# P04_USB_hub.net
KiCad netlist of a schematic drawn in Altium Designer
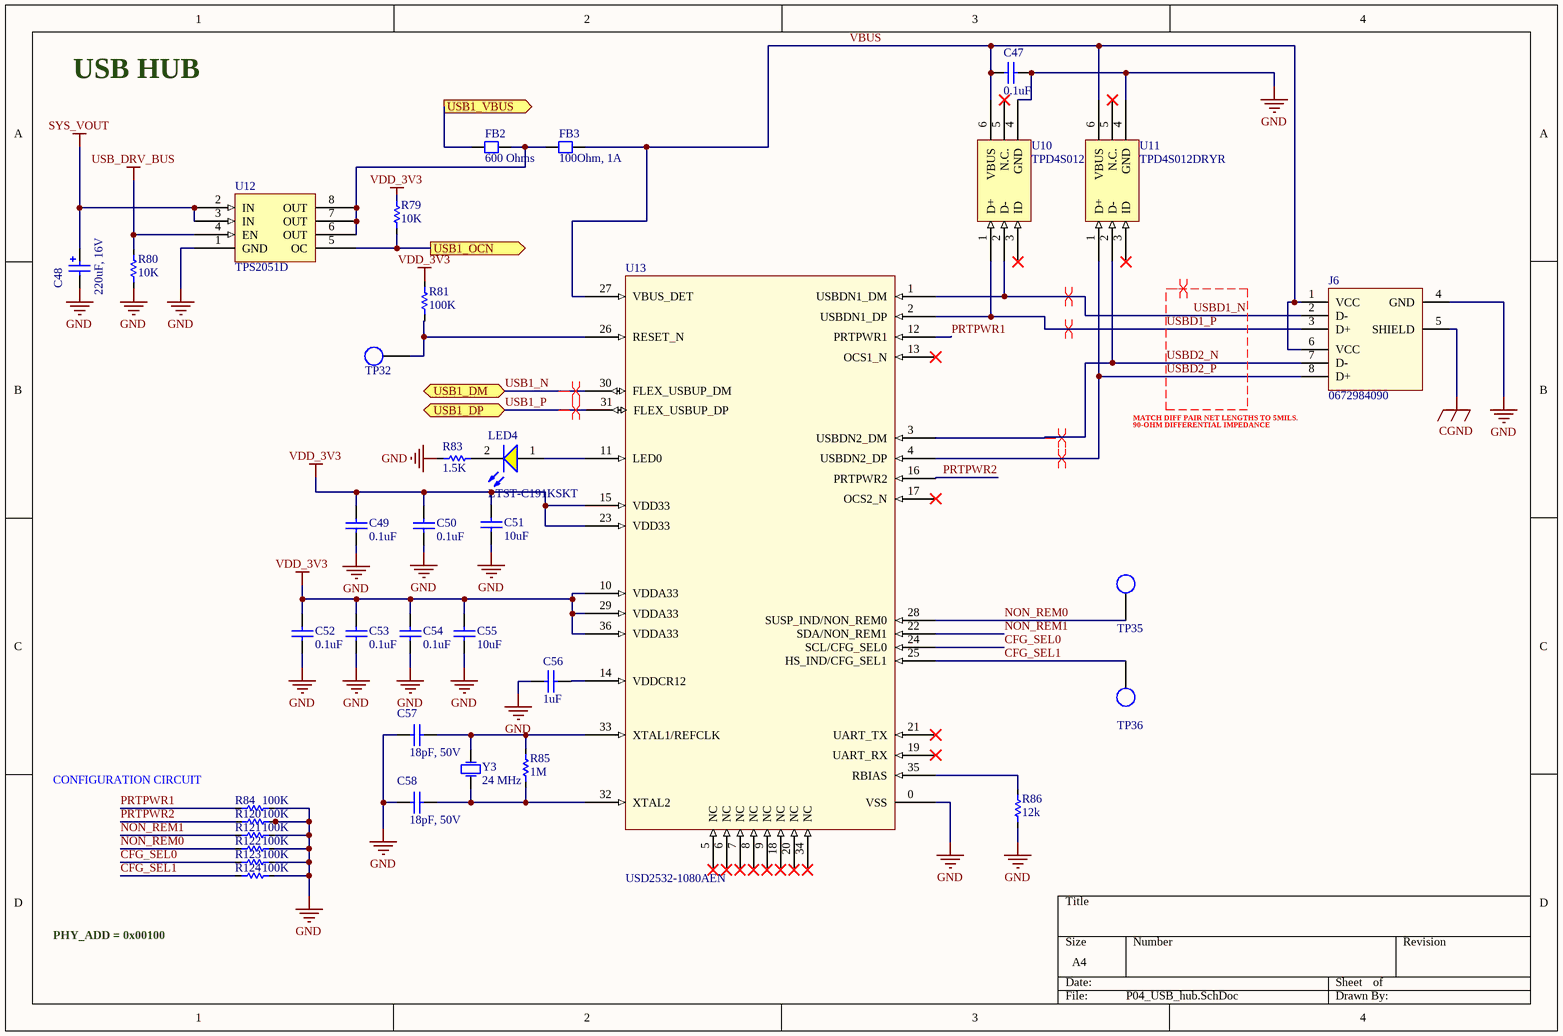
[diagram p0: P04_USB_hub.SchDoc]

(export (version "E")
  (design (tool "Eeschema 10.0.6"))
  (components
    (comp (ref "C47")
      (value "0.1uF")
      (footprint "CAP_0603")
      (description "CAP CER 0.1UF 16V X7R 0603")
      (fields (field (name "MANUFACTURER") "KEMET") (field (name "MANUFACTURER PART NO.") "C0603C104M4RACTU"))
      (libsource (lib "OSD335-X_Devboard") (part "C0603C104M4RACTU"))
    )
    (comp (ref "C48")
      (value "220uF, 16V")
      (footprint "CAP_SMD_6.3x7.7")
      (description "CAP 220 UF 20% 16 V")
      (fields
        (field (name "MANUFACTURER PART NO.") "865080345012")
        (field (name "MANUFACTURER") "Wurth Elektronik")
      )
      (libsource (lib "OSD335-X_Devboard") (part "865080345012"))
    )
    (comp (ref "C49")
      (value "0.1uF")
      (footprint "CAP_0603")
      (description "CAP CER 0.1UF 16V X7R 0603")
      (fields (field (name "MANUFACTURER") "KEMET") (field (name "MANUFACTURER PART NO.") "C0603C104M4RACTU"))
      (libsource (lib "OSD335-X_Devboard") (part "C0603C104M4RACTU"))
    )
    (comp (ref "C50")
      (value "0.1uF")
      (footprint "CAP_0603")
      (description "CAP CER 0.1UF 16V X7R 0603")
      (fields (field (name "MANUFACTURER") "KEMET") (field (name "MANUFACTURER PART NO.") "C0603C104M4RACTU"))
      (libsource (lib "OSD335-X_Devboard") (part "C0603C104M4RACTU"))
    )
    (comp (ref "C51")
      (value "10uF")
      (footprint "CAP_0603")
      (description "CAP CER 10UF 10V X5R 0603")
      (fields
        (field (name "MANUFACTURER") "KEMET")
        (field (name "MANUFACTURER PART NO.") "C0603C106M8PAC7867")
      )
      (libsource (lib "OSD335-X_Devboard") (part "C0603C106M8PAC7867"))
    )
    (comp (ref "C52")
      (value "0.1uF")
      (footprint "CAP_0603")
      (description "CAP CER 0.1UF 16V X7R 0603")
      (fields (field (name "MANUFACTURER") "KEMET") (field (name "MANUFACTURER PART NO.") "C0603C104M4RACTU"))
      (libsource (lib "OSD335-X_Devboard") (part "C0603C104M4RACTU"))
    )
    (comp (ref "C53")
      (value "0.1uF")
      (footprint "CAP_0603")
      (description "CAP CER 0.1UF 16V X7R 0603")
      (fields (field (name "MANUFACTURER") "KEMET") (field (name "MANUFACTURER PART NO.") "C0603C104M4RACTU"))
      (libsource (lib "OSD335-X_Devboard") (part "C0603C104M4RACTU"))
    )
    (comp (ref "C54")
      (value "0.1uF")
      (footprint "CAP_0603")
      (description "CAP CER 0.1UF 16V X7R 0603")
      (fields (field (name "MANUFACTURER") "KEMET") (field (name "MANUFACTURER PART NO.") "C0603C104M4RACTU"))
      (libsource (lib "OSD335-X_Devboard") (part "C0603C104M4RACTU"))
    )
    (comp (ref "C55")
      (value "10uF")
      (footprint "CAP_0603")
      (description "CAP CER 10UF 10V X5R 0603")
      (fields
        (field (name "MANUFACTURER") "KEMET")
        (field (name "MANUFACTURER PART NO.") "C0603C106M8PAC7867")
      )
      (libsource (lib "OSD335-X_Devboard") (part "C0603C106M8PAC7867"))
    )
    (comp (ref "C56")
      (value "1uF")
      (footprint "CAP_0603")
      (description "CAP CER 1UF 16V X7R 0603")
      (fields (field (name "MANUFACTURER") "KEMET") (field (name "MANUFACTURER PART NO.") "C0603C105M4RACTU"))
      (libsource (lib "OSD335-X_Devboard") (part "C0603C105M4RACTU"))
    )
    (comp (ref "C57")
      (value "18pF, 50V")
      (footprint "CAP_0603")
      (description "CAP CER 18PF 50V C0G/NP0 0603 +/- 0.5 PF")
      (fields (field (name "MANUFACTURER PART NO.") "C0603C180D5GACTU") (field (name "MANUFACTURER") "KEMET"))
      (libsource (lib "OSD335-X_Devboard") (part "C0603C180D5GACTU"))
    )
    (comp (ref "C58")
      (value "18pF, 50V")
      (footprint "CAP_0603")
      (description "CAP CER 18PF 50V C0G/NP0 0603 +/- 0.5 PF")
      (fields (field (name "MANUFACTURER PART NO.") "C0603C180D5GACTU") (field (name "MANUFACTURER") "KEMET"))
      (libsource (lib "OSD335-X_Devboard") (part "C0603C180D5GACTU"))
    )
    (comp (ref "FB2")
      (value "600 Ohms")
      (footprint "CAP_0603")
      (description "600 Ohms @ 100MHz Ferrite Bead 0603 2A 100mOhm")
      (fields
        (field (name "MANUFACTURER") "Chilisin Electronics")
        (field (name "MANUFACTURER PART NO.") "BBHV00160808601Y00")
      )
      (libsource (lib "Felix_Sch_lib") (part "BBHV00160808601Y00"))
    )
    (comp (ref "FB3")
      (value "100Ohm, 1A")
      (footprint "CAP_0603")
      (description "FERRITE BEAD 100 OHM 0603 1LN")
      (fields
        (field (name "MANUFACTURER PART NO.") "MPZ1608D101BTA00")
        (field (name "MANUFACTURER") "TDK Corporation")
      )
      (libsource (lib "OSD335-X_Devboard") (part "MPZ1608D101BTA00"))
    )
    (comp (ref "J6")
      (value "0672984090")
      (footprint "Dual USB Connector Molex")
      (description "CONN RCPT TYPEA STACKED 8POS R/A")
      (fields (field (name "MANUFACTURER") "Molex"))
      (libsource (lib "Felix_Sch_lib") (part "0672984090"))
    )
    (comp (ref "LED4")
      (value "LTST-C191KSKT")
      (footprint "LED_0603")
      (description "LED YELLOW CLEAR SMD 0603")
      (fields (field (name "MANUFACTURER") "Lite-On Inc."))
      (libsource (lib "Felix_Sch_lib") (part "LTST-C191KSKT"))
    )
    (comp (ref "R79")
      (value "10K")
      (footprint "RES_0603")
      (description "RES SMD 10K OHM 1% 1/10W 0603")
      (fields (field (name "TOLERANCE") "1%") (field (name "MANUFACTURER") "Yageo"))
      (libsource (lib "OSD335-X_Devboard") (part "RC0603FR-0710KL"))
    )
    (comp (ref "R80")
      (value "10K")
      (footprint "RES_0603")
      (description "RES SMD 10K OHM 1% 1/10W 0603")
      (fields (field (name "TOLERANCE") "1%") (field (name "MANUFACTURER") "Yageo"))
      (libsource (lib "OSD335-X_Devboard") (part "RC0603FR-0710KL"))
    )
    (comp (ref "R81")
      (value "100K")
      (footprint "RES_0603")
      (description "RES SMD 100K OHM 1% 1/10W 0603")
      (fields (field (name "TOLERANCE") "1%") (field (name "MANUFACTURER") "Yageo"))
      (libsource (lib "OSD335-X_Devboard") (part "RC0603FR-07100KL"))
    )
    (comp (ref "R83")
      (value "1.5K")
      (footprint "RES_0603")
      (description "RES SMD 1.5K OHM 1% 1/10W 0603")
      (fields (field (name "TOLERANCE") "1%") (field (name "MANUFACTURER") "Yageo"))
      (libsource (lib "OSD335-X_Devboard") (part "RC0603FR-071K5L"))
    )
    (comp (ref "R84")
      (value "100K")
      (footprint "RES_0603")
      (description "RES SMD 100K OHM 1% 1/10W 0603")
      (fields (field (name "TOLERANCE") "1%") (field (name "MANUFACTURER") "Yageo"))
      (libsource (lib "OSD335-X_Devboard") (part "RC0603FR-07100KL"))
    )
    (comp (ref "R85")
      (value "1M")
      (footprint "RES_0603")
      (description "RES SMD 1M OHM 5% 1/10W 0603")
      (fields (field (name "TOLERANCE") "5%") (field (name "MANUFACTURER") "Yageo"))
      (libsource (lib "OSD335-X_Devboard") (part "RC0603JR-071ML"))
    )
    (comp (ref "R86")
      (value "12k")
      (footprint "RES_0603")
      (description "RES 12K OHM 1% 1/10W 0603")
      (fields (field (name "TOLERANCE") "1%") (field (name "MANUFACTURER") "Stackpole Electronics Inc"))
      (libsource (lib "Felix_Sch_lib") (part "RMCF0603FT12K0"))
    )
    (comp (ref "R120")
      (value "100K")
      (footprint "RES_0603")
      (description "RES SMD 100K OHM 1% 1/10W 0603")
      (fields (field (name "TOLERANCE") "1%") (field (name "MANUFACTURER") "Yageo"))
      (libsource (lib "OSD335-X_Devboard") (part "RC0603FR-07100KL"))
    )
    (comp (ref "R121")
      (value "100K")
      (footprint "RES_0603")
      (description "RES SMD 100K OHM 1% 1/10W 0603")
      (fields (field (name "TOLERANCE") "1%") (field (name "MANUFACTURER") "Yageo"))
      (libsource (lib "OSD335-X_Devboard") (part "RC0603FR-07100KL"))
    )
    (comp (ref "R122")
      (value "100K")
      (footprint "RES_0603")
      (description "RES SMD 100K OHM 1% 1/10W 0603")
      (fields (field (name "TOLERANCE") "1%") (field (name "MANUFACTURER") "Yageo"))
      (libsource (lib "OSD335-X_Devboard") (part "RC0603FR-07100KL"))
    )
    (comp (ref "R123")
      (value "100K")
      (footprint "RES_0603")
      (description "RES SMD 100K OHM 1% 1/10W 0603")
      (fields (field (name "TOLERANCE") "1%") (field (name "MANUFACTURER") "Yageo"))
      (libsource (lib "OSD335-X_Devboard") (part "RC0603FR-07100KL"))
    )
    (comp (ref "R124")
      (value "100K")
      (footprint "RES_0603")
      (description "RES SMD 100K OHM 1% 1/10W 0603")
      (fields (field (name "TOLERANCE") "1%") (field (name "MANUFACTURER") "Yageo"))
      (libsource (lib "OSD335-X_Devboard") (part "RC0603FR-07100KL"))
    )
    (comp (ref "TP32")
      (value "TP_SMD")
      (footprint "TP_SMD")
      (libsource (lib "OSD335-X_Devboard") (part "TP_SMD"))
    )
    (comp (ref "TP35")
      (value "TP_SMD")
      (footprint "TP_SMD")
      (libsource (lib "OSD335-X_Devboard") (part "TP_SMD"))
    )
    (comp (ref "TP36")
      (value "TP_SMD")
      (footprint "TP_SMD")
      (libsource (lib "OSD335-X_Devboard") (part "TP_SMD"))
    )
    (comp (ref "U10")
      (value "TPD4S012DRYR")
      (footprint "Felix_PCB_lib:SON50P100X60-6N")
      (description "TVS DIODE 5.5V 6SON")
      (fields (field (name "MANUFACTURER") "Texas Instruments"))
      (libsource (lib "Felix_Sch_lib") (part "TPD4S012DRYR"))
    )
    (comp (ref "U11")
      (value "TPD4S012DRYR")
      (footprint "Felix_PCB_lib:SON50P100X60-6N")
      (description "TVS DIODE 5.5V 6SON")
      (fields (field (name "MANUFACTURER") "Texas Instruments"))
      (libsource (lib "Felix_Sch_lib") (part "TPD4S012DRYR"))
    )
    (comp (ref "U12")
      (value "TPS2051D")
      (footprint "Felix_PCB_lib:SOIC127P600X175-8N")
      (description "IC PWR SWITCH N-CHAN 1:1 8SOIC")
      (fields (field (name "MANUFACTURER") "Texas Instruments"))
      (libsource (lib "Felix_Sch_lib") (part "TPS2051D"))
    )
    (comp (ref "U13")
      (value "USD2532-1080AEN")
      (footprint "Felix_PCB_lib:DUAL_USB_HUB")
      (description "IC USB 2.0 HUB CTLR 2PORT 36SQFN")
      (fields
        (field (name "MANUFACTURER") "Microchip Technology")
        (field (name "MANUFACTURER PART NO.") "USB2532-1080AEN")
      )
      (libsource (lib "Felix_Sch_lib") (part "USD2532-1080AEN"))
    )
    (comp (ref "Y3")
      (value "24 MHz")
      (footprint "7A-24MHz")
      (description "CRYSTAL 24.0000MHZ 18PF SMD")
      (fields
        (field (name "MANUFACTURER") "TXC CORPORATION")
        (field (name "MANUFACTURER PART NO.") "7A-24.000MAAJ-T")
      )
      (libsource (lib "OSD335-X_Devboard") (part "7A-24.000MAAJ-T"))
    )
  )
  (nets
    (net (code "1") (name "/CFG_SEL0") (class "Default")
      (node (ref "R123") (pin "1") (pinfunction "1_1") (pintype "passive"))
      (node (ref "U13") (pin "24") (pinfunction "SCL/CFG_SEL0_24") (pintype "input"))
    )
    (net (code "2") (name "/CFG_SEL1") (class "Default")
      (node (ref "R124") (pin "1") (pinfunction "1_1") (pintype "passive"))
      (node (ref "TP36") (pin "1") (pinfunction "1_1") (pintype "passive"))
      (node (ref "U13") (pin "25") (pinfunction "HS_IND/CFG_SEL1_25") (pintype "input"))
    )
    (net (code "3") (name "/NON_REM0") (class "Default")
      (node (ref "R122") (pin "1") (pinfunction "1_1") (pintype "passive"))
      (node (ref "TP35") (pin "1") (pinfunction "1_1") (pintype "passive"))
      (node (ref "U13") (pin "28") (pinfunction "SUSP_IND/NON_REM0_28") (pintype "input"))
    )
    (net (code "4") (name "/NON_REM1") (class "Default")
      (node (ref "R121") (pin "1") (pinfunction "1_1") (pintype "passive"))
      (node (ref "U13") (pin "22") (pinfunction "SDA/NON_REM1_22") (pintype "input"))
    )
    (net (code "5") (name "/PRTPWR1") (class "Default")
      (node (ref "R84") (pin "1") (pinfunction "1_1") (pintype "passive"))
      (node (ref "U13") (pin "12") (pinfunction "PRTPWR1_12") (pintype "input"))
    )
    (net (code "6") (name "/PRTPWR2") (class "Default")
      (node (ref "R120") (pin "1") (pinfunction "1_1") (pintype "passive"))
      (node (ref "U13") (pin "16") (pinfunction "PRTPWR2_16") (pintype "input"))
    )
    (net (code "7") (name "/USB1_N") (class "Default")
      (node (ref "U13") (pin "30") (pinfunction "FLEX_USBUP_DM_30") (pintype "bidirectional"))
    )
    (net (code "8") (name "/USB1_OCN") (class "Default")
      (node (ref "R79") (pin "1") (pinfunction "1_1") (pintype "passive"))
      (node (ref "U12") (pin "5") (pinfunction "OC_5") (pintype "passive"))
    )
    (net (code "9") (name "/USB1_P") (class "Default")
      (node (ref "U13") (pin "31") (pinfunction "FLEX_USBUP_DP_31") (pintype "bidirectional"))
    )
    (net (code "10") (name "/USB1_VBUS") (class "Default")
      (node (ref "FB2") (pin "1") (pinfunction "1_1") (pintype "passive"))
    )
    (net (code "11") (name "/USBD1_N") (class "Default")
      (node (ref "J6") (pin "2") (pinfunction "D-_2") (pintype "passive"))
      (node (ref "U10") (pin "2") (pinfunction "D-_2") (pintype "input"))
      (node (ref "U13") (pin "1") (pinfunction "USBDN1_DM_1") (pintype "input"))
    )
    (net (code "12") (name "/USBD1_P") (class "Default")
      (node (ref "J6") (pin "3") (pinfunction "D+_3") (pintype "passive"))
      (node (ref "U10") (pin "1") (pinfunction "D+_1") (pintype "input"))
      (node (ref "U13") (pin "2") (pinfunction "USBDN1_DP_2") (pintype "input"))
    )
    (net (code "13") (name "/USBD2_N") (class "Default")
      (node (ref "J6") (pin "7") (pinfunction "D-_7") (pintype "passive"))
      (node (ref "U11") (pin "2") (pinfunction "D-_2") (pintype "input"))
      (node (ref "U13") (pin "3") (pinfunction "USBDN2_DM_3") (pintype "input"))
    )
    (net (code "14") (name "/USBD2_P") (class "Default")
      (node (ref "J6") (pin "8") (pinfunction "D+_8") (pintype "passive"))
      (node (ref "U11") (pin "1") (pinfunction "D+_1") (pintype "input"))
      (node (ref "U13") (pin "4") (pinfunction "USBDN2_DP_4") (pintype "input"))
    )
    (net (code "15") (name "/VBUS") (class "Default")
      (node (ref "C47") (pin "1") (pinfunction "1_1") (pintype "passive"))
      (node (ref "FB3") (pin "2") (pinfunction "2_2") (pintype "passive"))
      (node (ref "J6") (pin "1") (pinfunction "VCC_1") (pintype "passive"))
      (node (ref "J6") (pin "6") (pinfunction "VCC_6") (pintype "passive"))
      (node (ref "U10") (pin "6") (pinfunction "VBUS_6") (pintype "power_in"))
      (node (ref "U11") (pin "6") (pinfunction "VBUS_6") (pintype "power_in"))
      (node (ref "U13") (pin "27") (pinfunction "VBUS_DET_27") (pintype "input"))
    )
    (net (code "16") (name "CGND") (class "Default")
      (node (ref "J6") (pin "5") (pinfunction "SHIELD_5") (pintype "passive"))
    )
    (net (code "17") (name "GND") (class "Default")
      (node (ref "C47") (pin "2") (pinfunction "2_2") (pintype "passive"))
      (node (ref "C48") (pin "1") (pinfunction "N_1") (pintype "passive"))
      (node (ref "C49") (pin "1") (pinfunction "1_1") (pintype "passive"))
      (node (ref "C50") (pin "1") (pinfunction "1_1") (pintype "passive"))
      (node (ref "C51") (pin "1") (pinfunction "1_1") (pintype "passive"))
      (node (ref "C52") (pin "1") (pinfunction "1_1") (pintype "passive"))
      (node (ref "C53") (pin "1") (pinfunction "1_1") (pintype "passive"))
      (node (ref "C54") (pin "1") (pinfunction "1_1") (pintype "passive"))
      (node (ref "C55") (pin "1") (pinfunction "1_1") (pintype "passive"))
      (node (ref "C56") (pin "1") (pinfunction "1_1") (pintype "passive"))
      (node (ref "C57") (pin "1") (pinfunction "N_1") (pintype "passive"))
      (node (ref "C58") (pin "1") (pinfunction "N_1") (pintype "passive"))
      (node (ref "J6") (pin "4") (pinfunction "GND_4") (pintype "passive"))
      (node (ref "R120") (pin "2") (pinfunction "2_2") (pintype "passive"))
      (node (ref "R121") (pin "2") (pinfunction "2_2") (pintype "passive"))
      (node (ref "R122") (pin "2") (pinfunction "2_2") (pintype "passive"))
      (node (ref "R123") (pin "2") (pinfunction "2_2") (pintype "passive"))
      (node (ref "R124") (pin "2") (pinfunction "2_2") (pintype "passive"))
      (node (ref "R80") (pin "1") (pinfunction "1_1") (pintype "passive"))
      (node (ref "R83") (pin "1") (pinfunction "1_1") (pintype "passive"))
      (node (ref "R84") (pin "2") (pinfunction "2_2") (pintype "passive"))
      (node (ref "R86") (pin "1") (pinfunction "1_1") (pintype "passive"))
      (node (ref "U10") (pin "4") (pinfunction "GND_4") (pintype "power_in"))
      (node (ref "U11") (pin "4") (pinfunction "GND_4") (pintype "power_in"))
      (node (ref "U12") (pin "1") (pinfunction "GND_1") (pintype "power_in"))
      (node (ref "U13") (pin "0") (pinfunction "VSS_0") (pintype "power_in"))
    )
    (net (code "18") (name "Net-(C57-P)") (class "Default")
      (node (ref "C57") (pin "2") (pinfunction "P_2") (pintype "passive"))
      (node (ref "R85") (pin "2") (pinfunction "2_2") (pintype "passive"))
      (node (ref "U13") (pin "33") (pinfunction "XTAL1/REFCLK_33") (pintype "input"))
      (node (ref "Y3") (pin "2") (pinfunction "OSC2_2") (pintype "passive"))
    )
    (net (code "19") (name "Net-(C58-P)") (class "Default")
      (node (ref "C58") (pin "2") (pinfunction "P_2") (pintype "passive"))
      (node (ref "R85") (pin "1") (pinfunction "1_1") (pintype "passive"))
      (node (ref "U13") (pin "32") (pinfunction "XTAL2_32") (pintype "input"))
      (node (ref "Y3") (pin "1") (pinfunction "OSC1_1") (pintype "passive"))
    )
    (net (code "20") (name "Net-(FB2-Pad2)") (class "Default")
      (node (ref "FB2") (pin "2") (pinfunction "2_2") (pintype "passive"))
      (node (ref "FB3") (pin "1") (pinfunction "1_1") (pintype "passive"))
      (node (ref "U12") (pin "6") (pinfunction "OUT_6") (pintype "passive"))
      (node (ref "U12") (pin "7") (pinfunction "OUT_7") (pintype "passive"))
      (node (ref "U12") (pin "8") (pinfunction "OUT_8") (pintype "passive"))
    )
    (net (code "21") (name "Net-(LED4-A)") (class "Default")
      (node (ref "LED4") (pin "1") (pinfunction "A_1") (pintype "passive"))
      (node (ref "U13") (pin "11") (pinfunction "LED0_11") (pintype "input"))
    )
    (net (code "22") (name "Net-(LED4-C)") (class "Default")
      (node (ref "LED4") (pin "2") (pinfunction "C_2") (pintype "passive"))
      (node (ref "R83") (pin "2") (pinfunction "2_2") (pintype "passive"))
    )
    (net (code "23") (name "Net-(U13-RBIAS)") (class "Default")
      (node (ref "R86") (pin "2") (pinfunction "2_2") (pintype "passive"))
      (node (ref "U13") (pin "35") (pinfunction "RBIAS_35") (pintype "input"))
    )
    (net (code "24") (name "Net-(U13-RESET_N)") (class "Default")
      (node (ref "R81") (pin "1") (pinfunction "1_1") (pintype "passive"))
      (node (ref "TP32") (pin "1") (pinfunction "1_1") (pintype "passive"))
      (node (ref "U13") (pin "26") (pinfunction "RESET_N_26") (pintype "input"))
    )
    (net (code "25") (name "Net-(U13-VDDCR12)") (class "Default")
      (node (ref "C56") (pin "2") (pinfunction "2_2") (pintype "passive"))
      (node (ref "U13") (pin "14") (pinfunction "VDDCR12_14") (pintype "input"))
    )
    (net (code "26") (name "SYS_VOUT") (class "Default")
      (node (ref "C48") (pin "2") (pinfunction "P_2") (pintype "passive"))
      (node (ref "U12") (pin "2") (pinfunction "IN_2") (pintype "input"))
      (node (ref "U12") (pin "3") (pinfunction "IN_3") (pintype "input"))
    )
    (net (code "27") (name "USB_DRV_BUS") (class "Default")
      (node (ref "R80") (pin "2") (pinfunction "2_2") (pintype "passive"))
      (node (ref "U12") (pin "4") (pinfunction "EN_4") (pintype "input"))
    )
    (net (code "28") (name "VDD_3V3") (class "Default")
      (node (ref "C49") (pin "2") (pinfunction "2_2") (pintype "passive"))
      (node (ref "C50") (pin "2") (pinfunction "2_2") (pintype "passive"))
      (node (ref "C51") (pin "2") (pinfunction "2_2") (pintype "passive"))
      (node (ref "C52") (pin "2") (pinfunction "2_2") (pintype "passive"))
      (node (ref "C53") (pin "2") (pinfunction "2_2") (pintype "passive"))
      (node (ref "C54") (pin "2") (pinfunction "2_2") (pintype "passive"))
      (node (ref "C55") (pin "2") (pinfunction "2_2") (pintype "passive"))
      (node (ref "R79") (pin "2") (pinfunction "2_2") (pintype "passive"))
      (node (ref "R81") (pin "2") (pinfunction "2_2") (pintype "passive"))
      (node (ref "U13") (pin "10") (pinfunction "VDDA33_10") (pintype "input"))
      (node (ref "U13") (pin "15") (pinfunction "VDD33_15") (pintype "input"))
      (node (ref "U13") (pin "23") (pinfunction "VDD33_23") (pintype "input"))
      (node (ref "U13") (pin "29") (pinfunction "VDDA33_29") (pintype "input"))
      (node (ref "U13") (pin "36") (pinfunction "VDDA33_36") (pintype "input"))
    )
    (net (code "29") (name "unconnected-(U10-ID-Pad3)") (class "Default")
      (node (ref "U10") (pin "3") (pinfunction "ID_3") (pintype "input+no_connect"))
    )
    (net (code "30") (name "unconnected-(U10-N.C.-Pad5)") (class "Default")
      (node (ref "U10") (pin "5") (pinfunction "N.C._5") (pintype "passive+no_connect"))
    )
    (net (code "31") (name "unconnected-(U11-ID-Pad3)") (class "Default")
      (node (ref "U11") (pin "3") (pinfunction "ID_3") (pintype "input+no_connect"))
    )
    (net (code "32") (name "unconnected-(U11-N.C.-Pad5)") (class "Default")
      (node (ref "U11") (pin "5") (pinfunction "N.C._5") (pintype "passive+no_connect"))
    )
    (net (code "33") (name "unconnected-(U13-NC-Pad5)") (class "Default")
      (node (ref "U13") (pin "5") (pinfunction "NC_5") (pintype "input+no_connect"))
    )
    (net (code "34") (name "unconnected-(U13-NC-Pad6)") (class "Default")
      (node (ref "U13") (pin "6") (pinfunction "NC_6") (pintype "input+no_connect"))
    )
    (net (code "35") (name "unconnected-(U13-NC-Pad7)") (class "Default")
      (node (ref "U13") (pin "7") (pinfunction "NC_7") (pintype "input+no_connect"))
    )
    (net (code "36") (name "unconnected-(U13-NC-Pad8)") (class "Default")
      (node (ref "U13") (pin "8") (pinfunction "NC_8") (pintype "input+no_connect"))
    )
    (net (code "37") (name "unconnected-(U13-NC-Pad9)") (class "Default")
      (node (ref "U13") (pin "9") (pinfunction "NC_9") (pintype "input+no_connect"))
    )
    (net (code "38") (name "unconnected-(U13-NC-Pad18)") (class "Default")
      (node (ref "U13") (pin "18") (pinfunction "NC_18") (pintype "input+no_connect"))
    )
    (net (code "39") (name "unconnected-(U13-NC-Pad20)") (class "Default")
      (node (ref "U13") (pin "20") (pinfunction "NC_20") (pintype "input+no_connect"))
    )
    (net (code "40") (name "unconnected-(U13-NC-Pad34)") (class "Default")
      (node (ref "U13") (pin "34") (pinfunction "NC_34") (pintype "input+no_connect"))
    )
    (net (code "41") (name "unconnected-(U13-OCS1_N-Pad13)") (class "Default")
      (node (ref "U13") (pin "13") (pinfunction "OCS1_N_13") (pintype "input+no_connect"))
    )
    (net (code "42") (name "unconnected-(U13-OCS2_N-Pad17)") (class "Default")
      (node (ref "U13") (pin "17") (pinfunction "OCS2_N_17") (pintype "input+no_connect"))
    )
    (net (code "43") (name "unconnected-(U13-UART_RX-Pad19)") (class "Default")
      (node (ref "U13") (pin "19") (pinfunction "UART_RX_19") (pintype "input+no_connect"))
    )
    (net (code "44") (name "unconnected-(U13-UART_TX-Pad21)") (class "Default")
      (node (ref "U13") (pin "21") (pinfunction "UART_TX_21") (pintype "input+no_connect"))
    )
  )
)
